# Peripherals.net
KiCad netlist of a schematic drawn in Altium Designer
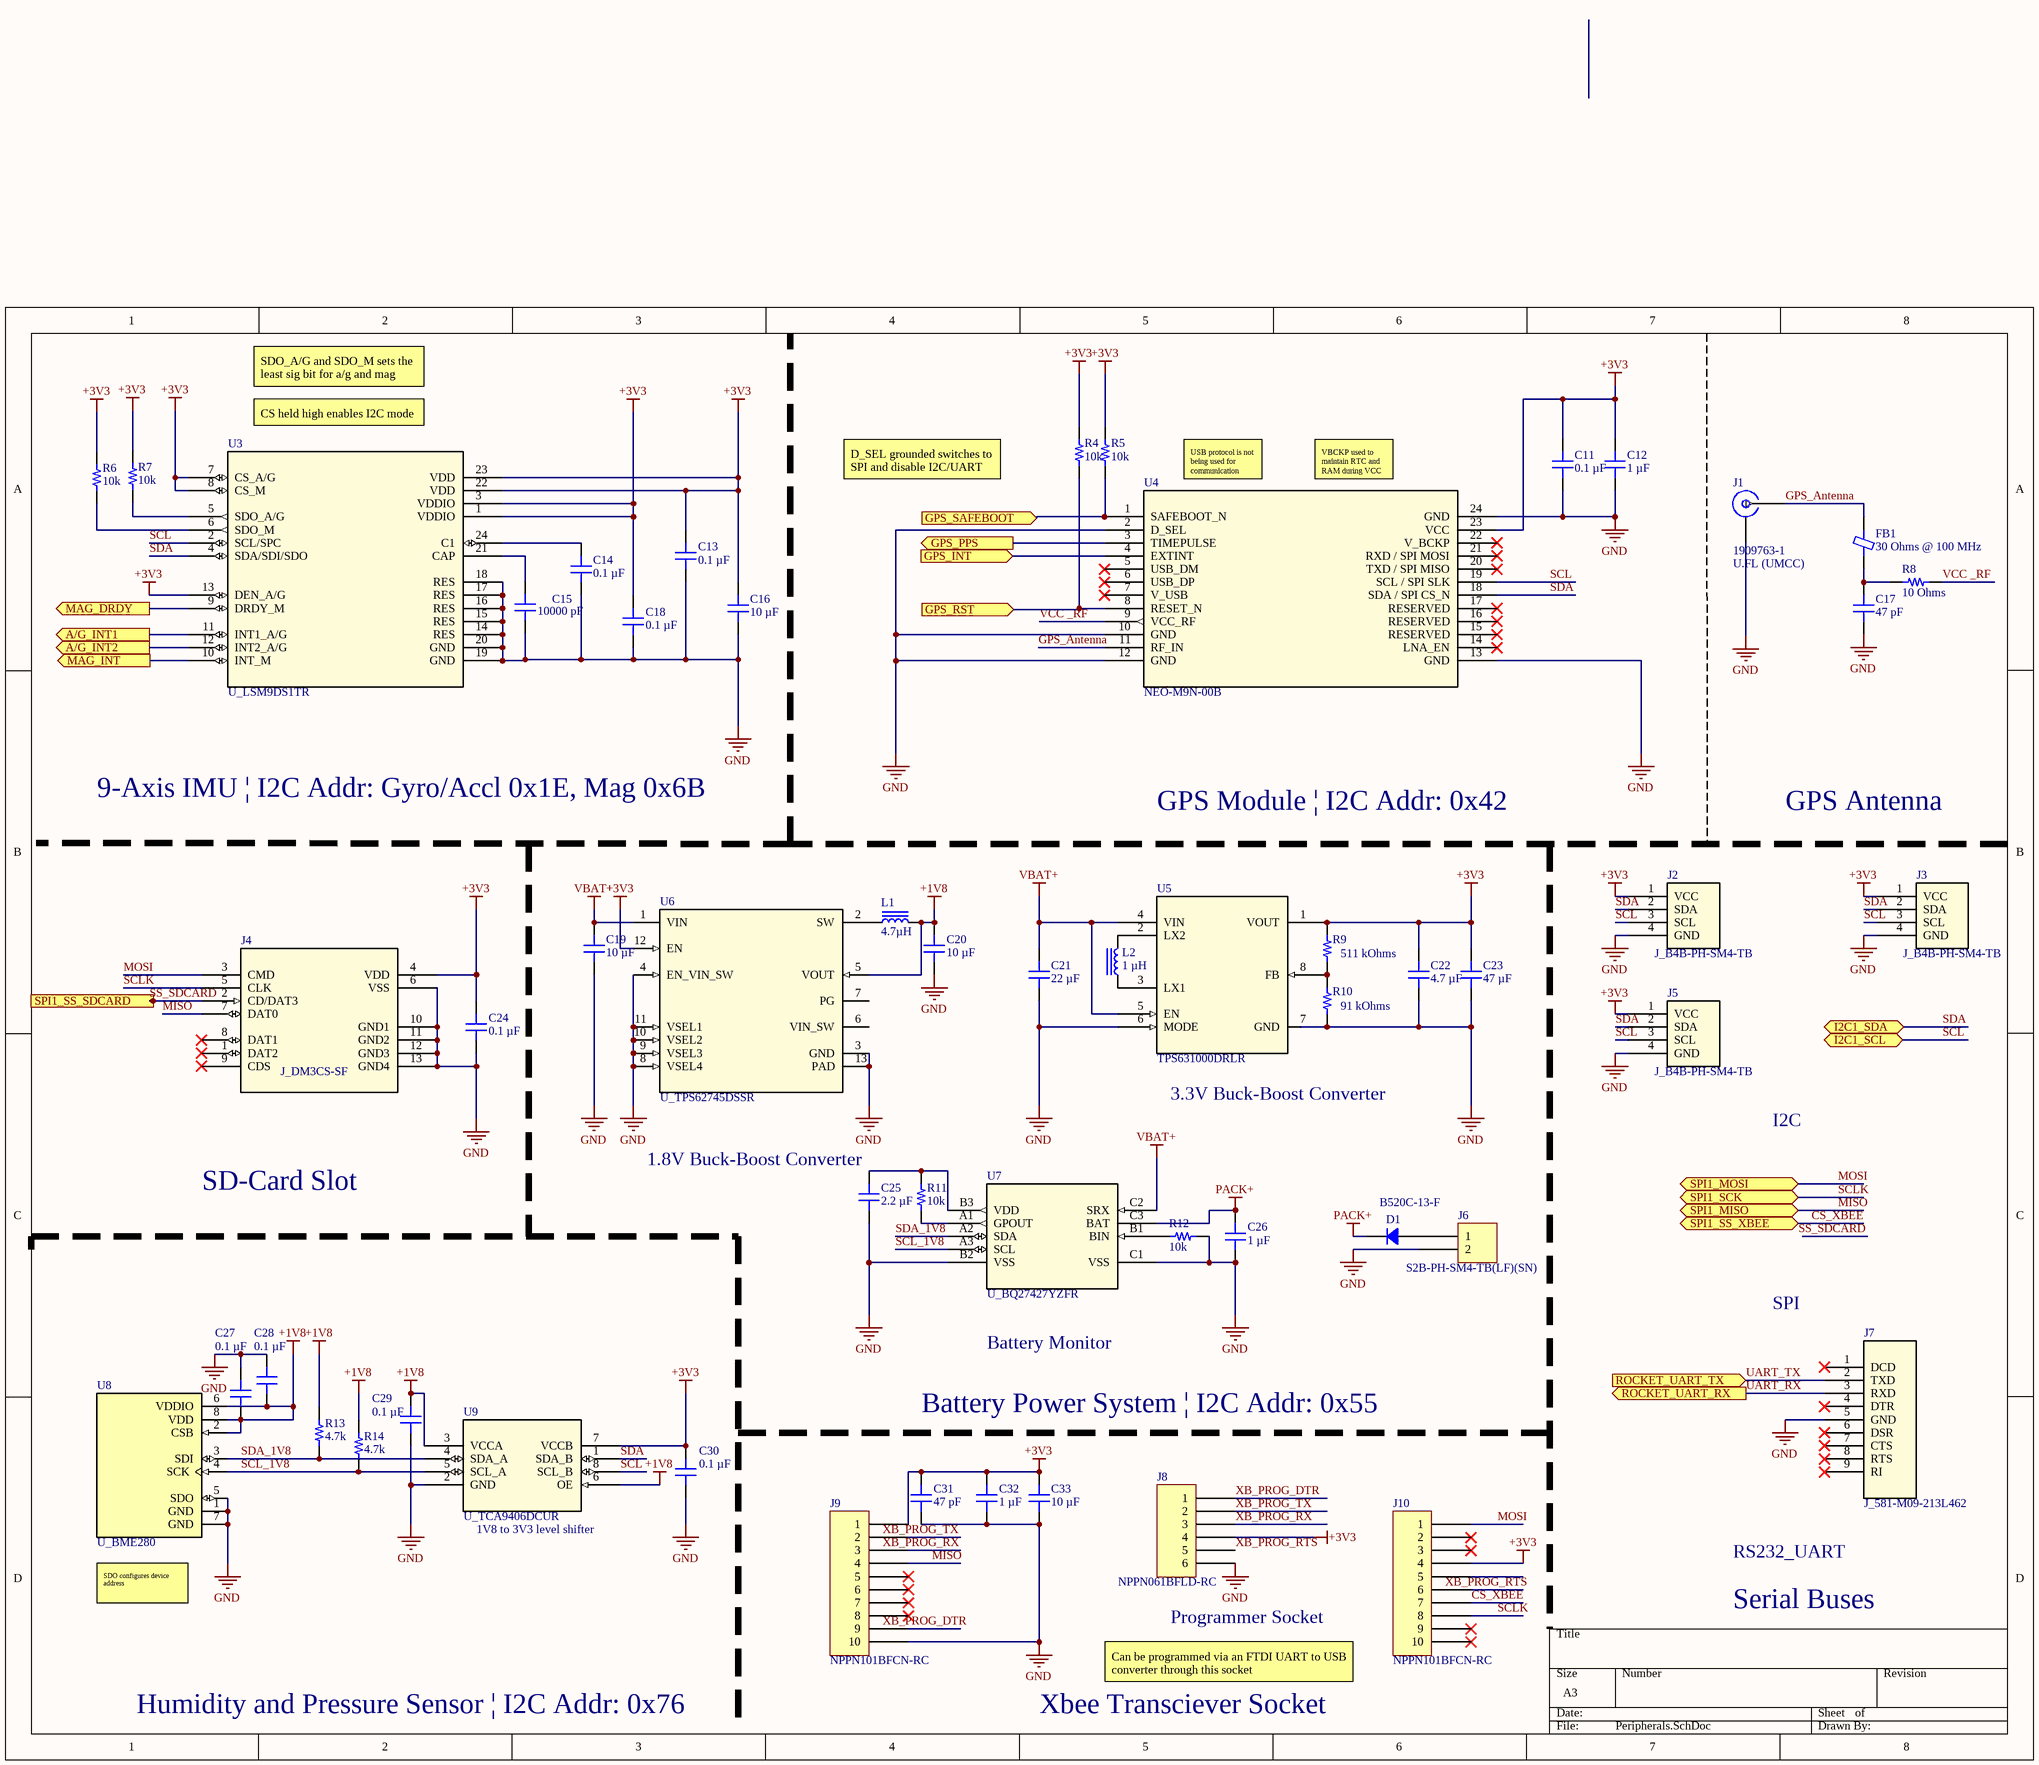
[diagram p0: Peripherals.SchDoc]

(export (version "E")
  (design (tool "Eeschema 10.0.6"))
  (components
    (comp (ref "C11")
      (value "0.1 µF")
      (footprint "CAP 0402_1005")
      (description "CAP CER 100NF 10V X7R 0402")
      (fields
        (field (name "PART NUMBER") "CL05B104KP5VPNC")
        (field (name "MANUFACTURER") "Samsung Electro-Mechanics")
      )
      (libsource (lib "Celestial Altium Library - altium_library") (part "Capacitor"))
    )
    (comp (ref "C12")
      (value "1 µF")
      (footprint "CAP 0402_1005")
      (description "CAP CER 1UF 4V X5R 0402")
      (fields (field (name "PART NUMBER") "KGM05AR50G105KH") (field (name "MANUFACTURER") "KYOCERA AVX"))
      (libsource (lib "Celestial Altium Library - altium_library") (part "Capacitor"))
    )
    (comp (ref "C13")
      (value "0.1 µF")
      (footprint "CAP 0201_0603")
      (description "0201 6.3V X7R 100NF 10%")
      (fields (field (name "PART NUMBER") "02016C104KAT2A") (field (name "MANUFACTURER") "KYOCERA AVX"))
      (libsource (lib "Celestial Altium Library - altium_library") (part "Capacitor"))
    )
    (comp (ref "C14")
      (value "0.1 µF")
      (footprint "CAP 0402_1005")
      (description "CAP CER 100NF 10V X7R 0402")
      (fields
        (field (name "PART NUMBER") "CL05B104KP5VPNC")
        (field (name "MANUFACTURER") "Samsung Electro-Mechanics")
      )
      (libsource (lib "Celestial Altium Library - altium_library") (part "Capacitor"))
    )
    (comp (ref "C15")
      (value "10000 pF")
      (footprint "CAP 0402_1005")
      (description "CAP CER 0402 10NF 16V X7R 10%")
      (fields (field (name "PART NUMBER") "C0402C103K4REC7867") (field (name "MANUFACTURER") "KEMET"))
      (libsource (lib "Celestial Altium Library - altium_library") (part "Capacitor"))
    )
    (comp (ref "C16")
      (value "10 µF")
      (footprint "CAP 0402_1005")
      (description "CAP CER 10UF 4V X5R 0402")
      (fields
        (field (name "PART NUMBER") "GRM155R60G106ME01D")
        (field (name "MANUFACTURER") "Murata Electronics")
      )
      (libsource (lib "Celestial Altium Library - altium_library") (part "Capacitor"))
    )
    (comp (ref "C17")
      (value "47 pF")
      (footprint "CAP 0402_1005")
      (description "CAP CER 47PF 16V NP0 0402")
      (fields (field (name "PART NUMBER") "C0402C470J4GAC7867") (field (name "MANUFACTURER") "KEMET"))
      (libsource (lib "Celestial Altium Library - altium_library") (part "Capacitor"))
    )
    (comp (ref "C18")
      (value "0.1 µF")
      (footprint "CAP 0201_0603")
      (description "0201 6.3V X7R 100NF 10%")
      (fields (field (name "PART NUMBER") "02016C104KAT2A") (field (name "MANUFACTURER") "KYOCERA AVX"))
      (libsource (lib "Celestial Altium Library - altium_library") (part "Capacitor"))
    )
    (comp (ref "C19")
      (value "10 µF")
      (footprint "CAP 0402_1005")
      (description "CAP CER 10UF 4V X5R 0402")
      (fields
        (field (name "PART NUMBER") "GRM155R60G106ME01D")
        (field (name "MANUFACTURER") "Murata Electronics")
      )
      (libsource (lib "Celestial Altium Library - altium_library") (part "Capacitor"))
    )
    (comp (ref "C20")
      (value "10 µF")
      (footprint "CAP 0402_1005")
      (description "CAP CER 10UF 4V X5R 0402")
      (fields
        (field (name "PART NUMBER") "GRM155R60G106ME01D")
        (field (name "MANUFACTURER") "Murata Electronics")
      )
      (libsource (lib "Celestial Altium Library - altium_library") (part "Capacitor"))
    )
    (comp (ref "C21")
      (value "22 µF")
      (footprint "CAP 0402_1005")
      (description "CAP CER 22UF 10V X5R 0402")
      (fields
        (field (name "PART NUMBER") "GRM158R61A226ME15D")
        (field (name "MANUFACTURER") "Murata Electronics")
      )
      (libsource (lib "Celestial Altium Library - altium_library") (part "Capacitor"))
    )
    (comp (ref "C22")
      (value "4.7 µF")
      (footprint "CAP 0603_1608")
      (description "CAP CER 4.7UF 6.3V X6S 0603")
      (fields
        (field (name "PART NUMBER") "GRM185C80J475ME11D")
        (field (name "MANUFACTURER") "Murata Electronics")
      )
      (libsource (lib "Celestial Altium Library - altium_library") (part "Capacitor"))
    )
    (comp (ref "C23")
      (value "47 µF")
      (footprint "CAP 0805_2012")
      (description "CAP CER 47UF 4V X5R 0805")
      (fields (field (name "PART NUMBER") "AMK212BBJ476MD-T") (field (name "MANUFACTURER") "Taiyo Yuden"))
      (libsource (lib "Celestial Altium Library - altium_library") (part "Capacitor"))
    )
    (comp (ref "C24")
      (value "0.1 µF")
      (footprint "CAP 0402_1005")
      (description "CAP CER 100NF 10V X7R 0402")
      (fields
        (field (name "PART NUMBER") "CL05B104KP5VPNC")
        (field (name "MANUFACTURER") "Samsung Electro-Mechanics")
      )
      (libsource (lib "Celestial Altium Library - altium_library") (part "Capacitor"))
    )
    (comp (ref "C25")
      (value "2.2 µF")
      (footprint "CAP 0402_1005")
      (description "CAP CER 2.2UF 35V X5R 0402")
      (fields
        (field (name "PART NUMBER") "GRM155R6YA225KE11D")
        (field (name "MANUFACTURER") "Murata Electronics")
      )
      (libsource (lib "Celestial Altium Library - altium_library") (part "Capacitor"))
    )
    (comp (ref "C26")
      (value "1 µF")
      (footprint "CAP 0402_1005")
      (description "CAP CER 1UF 4V X5R 0402")
      (fields (field (name "PART NUMBER") "KGM05AR50G105KH") (field (name "MANUFACTURER") "KYOCERA AVX"))
      (libsource (lib "Celestial Altium Library - altium_library") (part "Capacitor"))
    )
    (comp (ref "C27")
      (value "0.1 µF")
      (footprint "CAP 0402_1005")
      (description "CAP CER 100NF 10V X7R 0402")
      (fields
        (field (name "PART NUMBER") "CL05B104KP5VPNC")
        (field (name "MANUFACTURER") "Samsung Electro-Mechanics")
      )
      (libsource (lib "Celestial Altium Library - altium_library") (part "Capacitor"))
    )
    (comp (ref "C28")
      (value "0.1 µF")
      (footprint "CAP 0402_1005")
      (description "CAP CER 100NF 10V X7R 0402")
      (fields
        (field (name "PART NUMBER") "CL05B104KP5VPNC")
        (field (name "MANUFACTURER") "Samsung Electro-Mechanics")
      )
      (libsource (lib "Celestial Altium Library - altium_library") (part "Capacitor"))
    )
    (comp (ref "C29")
      (value "0.1 µF")
      (footprint "CAP 0402_1005")
      (description "CAP CER 100NF 10V X7R 0402")
      (fields
        (field (name "PART NUMBER") "CL05B104KP5VPNC")
        (field (name "MANUFACTURER") "Samsung Electro-Mechanics")
      )
      (libsource (lib "Celestial Altium Library - altium_library") (part "Capacitor"))
    )
    (comp (ref "C30")
      (value "0.1 µF")
      (footprint "CAP 0402_1005")
      (description "CAP CER 100NF 10V X7R 0402")
      (fields
        (field (name "PART NUMBER") "CL05B104KP5VPNC")
        (field (name "MANUFACTURER") "Samsung Electro-Mechanics")
      )
      (libsource (lib "Celestial Altium Library - altium_library") (part "Capacitor"))
    )
    (comp (ref "C31")
      (value "47 pF")
      (footprint "CAP 0402_1005")
      (description "CAP CER 47PF 16V NP0 0402")
      (fields (field (name "PART NUMBER") "C0402C470J4GAC7867") (field (name "MANUFACTURER") "KEMET"))
      (libsource (lib "Celestial Altium Library - altium_library") (part "Capacitor"))
    )
    (comp (ref "C32")
      (value "1 µF")
      (footprint "CAP 0402_1005")
      (description "CAP CER 1UF 4V X5R 0402")
      (fields (field (name "PART NUMBER") "KGM05AR50G105KH") (field (name "MANUFACTURER") "KYOCERA AVX"))
      (libsource (lib "Celestial Altium Library - altium_library") (part "Capacitor"))
    )
    (comp (ref "C33")
      (value "10 µF")
      (footprint "CAP 0402_1005")
      (description "CAP CER 10UF 10V X5R 0402")
      (fields
        (field (name "PART NUMBER") "CL05A106MP8NUB8")
        (field (name "MANUFACTURER") "Samsung Electro-Mechanics")
      )
      (libsource (lib "Celestial Altium Library - altium_library") (part "Capacitor"))
    )
    (comp (ref "D1")
      (value "B520C-13-F")
      (footprint "DO214AB SMC")
      (description "DIODE SCHOTTKY 20V 5A SMC")
      (fields (field (name "MANUFACTURER") "Diodes Incorporated"))
      (libsource (lib "Celestial Altium Library - altium_library") (part "Diode"))
    )
    (comp (ref "FB1")
      (value "30 Ohms @ 100 MHz")
      (footprint "FER 0402_1005")
      (description "FERRITE BEAD 30 OHM 0402 1LN")
      (fields
        (field (name "PART NUMBER") "BLM15PE300SH1D")
        (field (name "MANUFACTURER") "Murata Electronics")
      )
      (libsource (lib "Celestial Altium Library - altium_library") (part "Ferrite Chip"))
    )
    (comp (ref "J1")
      (value "1909763-1")
      (footprint "TE C-1909763")
      (description "CONN UMCC JACK STR 50OHM SMD")
      (fields
        (field (name "CONNECTOR STYLE") "U.FL (UMCC)")
        (field (name "MANUFACTURER") "TE Connectivity AMP Connectors")
      )
      (libsource (lib "Celestial Altium Library - altium_library") (part "COAXIAL JACK"))
    )
    (comp (ref "J2")
      (value "J_B4B-PH-SM4-TB")
      (footprint "CONN_B4B-PH-SM4-TB_JST")
      (description "No Description Available")
      (libsource (lib "J_B4B-PH-SM4-TB") (part "J_B4B-PH-SM4-TB"))
    )
    (comp (ref "J3")
      (value "J_B4B-PH-SM4-TB")
      (footprint "CONN_B4B-PH-SM4-TB_JST")
      (description "No Description Available")
      (libsource (lib "J_B4B-PH-SM4-TB") (part "J_B4B-PH-SM4-TB"))
    )
    (comp (ref "J4")
      (value "J_DM3CS-SF")
      (footprint "DM3CS-SF_HIR")
      (description "No Description Available")
      (libsource (lib "J_DM3CS-SF") (part "J_DM3CS-SF"))
    )
    (comp (ref "J5")
      (value "J_B4B-PH-SM4-TB")
      (footprint "CONN_B4B-PH-SM4-TB_JST")
      (description "No Description Available")
      (libsource (lib "J_B4B-PH-SM4-TB") (part "J_B4B-PH-SM4-TB"))
    )
    (comp (ref "J6")
      (value "S2B-PH-SM4-TB(LF)(SN)")
      (footprint "JST S2B-PH-SM4-TB")
      (description "CONN HEADER SMD R/A 2POS 2MM")
      (fields (field (name "MANUFACTURER") "JST Sales America Inc."))
      (libsource (lib "Celestial Altium Library - altium_library") (part "2 Pin"))
    )
    (comp (ref "J7")
      (value "J_581-M09-213L462")
      (footprint "CONN_581-M09-213L462_NRC")
      (description "9 Position D-Type, Micro-D Receptacle, Female Sockets Connector")
      (libsource (lib "J_581-M09-213L462") (part "J_581-M09-213L462"))
    )
    (comp (ref "J8")
      (value "NPPN061BFLD-RC")
      (footprint "SULLINS NPPN061BFLD-RC")
      (description "CONN HDR 6POS 0.079 GOLD SMD")
      (fields (field (name "MANUFACTURER") "Sullins Connector Solutions"))
      (libsource (lib "Celestial Altium Library - altium_library") (part "6 Pin"))
    )
    (comp (ref "J9")
      (value "NPPN101BFCN-RC")
      (footprint "SULLINS NPPN101BFCN")
      (description "CONN HDR 10POS 0.079 GOLD PCB")
      (fields (field (name "MANUFACTURER") "Sullins Connector Solutions"))
      (libsource (lib "Celestial Altium Library - altium_library") (part "10 Pin"))
    )
    (comp (ref "J10")
      (value "NPPN101BFCN-RC")
      (footprint "SULLINS NPPN101BFCN")
      (description "CONN HDR 10POS 0.079 GOLD PCB")
      (fields (field (name "MANUFACTURER") "Sullins Connector Solutions"))
      (libsource (lib "Celestial Altium Library - altium_library") (part "10 Pin"))
    )
    (comp (ref "L1")
      (value "4.7µH")
      (footprint "IND 0603_1608 RF WW")
      (description "FIXED IND 4.7UH 160MA 2.7 OHM")
      (fields (field (name "PART NUMBER") "AISC-0603F-4R7J-T") (field (name "MANUFACTURER") "Abracon LLC"))
      (libsource (lib "Celestial Altium Library - altium_library") (part "Inductor"))
    )
    (comp (ref "L2")
      (value "1 µH")
      (footprint "IND 0806_2016")
      (description "FIXED IND 1UH 1.4A 107 MOHM SMD")
      (fields
        (field (name "PART NUMBER") "LQM2MPN1R0NG0L")
        (field (name "MANUFACTURER") "Murata Electronics")
      )
      (libsource (lib "Celestial Altium Library - altium_library") (part "Inductor"))
    )
    (comp (ref "R4")
      (value "10k")
      (footprint "RES 0402_1005")
      (description "RES 10K OHM 0.1% 1/10W 0402")
      (fields
        (field (name "PART NUMBER") "RP73PF1E10KBTD")
        (field (name "MANUFACTURER") "TE Connectivity Passive Product")
      )
      (libsource (lib "Celestial Altium Library - altium_library") (part "Resistor"))
    )
    (comp (ref "R5")
      (value "10k")
      (footprint "RES 0402_1005")
      (description "RES 10K OHM 0.1% 1/10W 0402")
      (fields
        (field (name "PART NUMBER") "RP73PF1E10KBTD")
        (field (name "MANUFACTURER") "TE Connectivity Passive Product")
      )
      (libsource (lib "Celestial Altium Library - altium_library") (part "Resistor"))
    )
    (comp (ref "R6")
      (value "10k")
      (footprint "RES 0402_1005")
      (description "RES 10K OHM 0.1% 1/10W 0402")
      (fields
        (field (name "PART NUMBER") "RP73PF1E10KBTD")
        (field (name "MANUFACTURER") "TE Connectivity Passive Product")
      )
      (libsource (lib "Celestial Altium Library - altium_library") (part "Resistor"))
    )
    (comp (ref "R7")
      (value "10k")
      (footprint "RES 0402_1005")
      (description "RES 10K OHM 0.1% 1/10W 0402")
      (fields
        (field (name "PART NUMBER") "RP73PF1E10KBTD")
        (field (name "MANUFACTURER") "TE Connectivity Passive Product")
      )
      (libsource (lib "Celestial Altium Library - altium_library") (part "Resistor"))
    )
    (comp (ref "R8")
      (value "10 Ohms")
      (footprint "RES 0402_1005")
      (description "TOTAL LEAD-FREE CHIP RESISTOR SU")
      (fields (field (name "PART NUMBER") "SR0402JR-7W10RP") (field (name "MANUFACTURER") "Yageo"))
      (libsource (lib "Celestial Altium Library - altium_library") (part "Resistor"))
    )
    (comp (ref "R9")
      (value "511 kOhms")
      (footprint "RES 0402_1005")
      (description "RES SMD 511K OHM 1% 1/16W 0402")
      (fields (field (name "PART NUMBER") "CRCW0402511KFKED") (field (name "MANUFACTURER") "Vishay Dale"))
      (libsource (lib "Celestial Altium Library - altium_library") (part "Resistor"))
    )
    (comp (ref "R10")
      (value "91 kOhms")
      (footprint "RES 0402_1005")
      (description "RES SMD 91K OHM 5% 1/16W 0402")
      (fields (field (name "PART NUMBER") "CRCW040291K0JNED") (field (name "MANUFACTURER") "Vishay Dale"))
      (libsource (lib "Celestial Altium Library - altium_library") (part "Resistor"))
    )
    (comp (ref "R11")
      (value "10k")
      (footprint "RES 0402_1005")
      (description "RES 10K OHM 0.1% 1/10W 0402")
      (fields
        (field (name "PART NUMBER") "RP73PF1E10KBTD")
        (field (name "MANUFACTURER") "TE Connectivity Passive Product")
      )
      (libsource (lib "Celestial Altium Library - altium_library") (part "Resistor"))
    )
    (comp (ref "R12")
      (value "10k")
      (footprint "RES 0402_1005")
      (description "RES 10K OHM 0.1% 1/10W 0402")
      (fields
        (field (name "PART NUMBER") "RP73PF1E10KBTD")
        (field (name "MANUFACTURER") "TE Connectivity Passive Product")
      )
      (libsource (lib "Celestial Altium Library - altium_library") (part "Resistor"))
    )
    (comp (ref "R13")
      (value "4.7k")
      (footprint "RES 0201_0603")
      (description "RES SMD 4.7K OHM 1% 1/20W 0201")
      (fields (field (name "PART NUMBER") "CRCW02014K70FKED") (field (name "MANUFACTURER") "Vishay Dale"))
      (libsource (lib "Celestial Altium Library - altium_library") (part "Resistor"))
    )
    (comp (ref "R14")
      (value "4.7k")
      (footprint "RES 0201_0603")
      (description "RES SMD 4.7K OHM 1% 1/20W 0201")
      (fields (field (name "PART NUMBER") "CRCW02014K70FKED") (field (name "MANUFACTURER") "Vishay Dale"))
      (libsource (lib "Celestial Altium Library - altium_library") (part "Resistor"))
    )
    (comp (ref "U3")
      (value "U_LSM9DS1TR")
      (footprint "LGA-24_3X3P5X1_STM")
      (description "No Description Available")
      (libsource (lib "U_LSM9DS1TR") (part "U_LSM9DS1TR"))
    )
    (comp (ref "U4")
      (value "NEO-M9N-00B")
      (footprint "XCVR_NEO-M9N-00B")
      (libsource (lib "U_NEO-M9N-00B") (part "U_NEO-M9N-00B"))
    )
    (comp (ref "U5")
      (value "TPS631000DRLR")
      (footprint "TPS631000DRLR_TEX")
      (description "Non-Isolated PoL Module DC DC Converter 1 Output 1.2 ~ 5.3V 2A 1.6V - 5.5V Input")
      (libsource (lib "U_TPS631000DRLR") (part "TPS631000DRLR"))
    )
    (comp (ref "U6")
      (value "U_TPS62745DSSR")
      (footprint "DSS0012A")
      (description "No Description Available")
      (fields (field (name "PARTNUMBER") "TPS62745DSSR") (field (name "ALTERNATE_PARTNUMBER") "TPS62745DSST"))
      (libsource (lib "U_TPS62745DSSR") (part "U_TPS62745DSSR"))
    )
    (comp (ref "U7")
      (value "U_BQ27427YZFR")
      (footprint "DSBGA9-YZF_TEX")
      (description "No Description Available")
      (libsource (lib "U_BQ27427YZFR") (part "U_BQ27427YZFR"))
    )
    (comp (ref "U8")
      (value "U_BME280")
      (footprint "BME280")
      (description "Humidity, Pressure, Temperature 0 ~ 100% RH I2C, SPI ±3% 1 s Surface Mount")
      (fields (field (name "MP") "BME280"))
      (libsource (lib "U_BME280") (part "U_BME280"))
    )
    (comp (ref "U9")
      (value "U_TCA9406DCUR")
      (footprint "DCU8")
      (description "No Description Available")
      (libsource (lib "U_TCA9406DCUR") (part "U_TCA9406DCUR"))
    )
  )
  (nets
    (net (code "1") (name "+1V8") (class "Default")
      (node (ref "C20") (pin "2") (pinfunction "2_2") (pintype "passive"))
      (node (ref "C27") (pin "2") (pinfunction "2_2") (pintype "passive"))
      (node (ref "C28") (pin "2") (pinfunction "2_2") (pintype "passive"))
      (node (ref "C29") (pin "1") (pinfunction "1_1") (pintype "passive"))
      (node (ref "L1") (pin "2") (pinfunction "2_2") (pintype "passive"))
      (node (ref "R13") (pin "2") (pinfunction "2_2") (pintype "passive"))
      (node (ref "R14") (pin "2") (pinfunction "2_2") (pintype "passive"))
      (node (ref "U6") (pin "5") (pinfunction "VOUT_5") (pintype "input"))
      (node (ref "U8") (pin "2") (pinfunction "CSB_2") (pintype "input"))
      (node (ref "U8") (pin "6") (pinfunction "VDDIO_6") (pintype "power_in"))
      (node (ref "U8") (pin "8") (pinfunction "VDD_8") (pintype "power_in"))
      (node (ref "U9") (pin "3") (pinfunction "VCCA_3") (pintype "power_in"))
      (node (ref "U9") (pin "6") (pinfunction "OE_6") (pintype "input"))
    )
    (net (code "2") (name "+3V3") (class "Default")
      (node (ref "C11") (pin "1") (pinfunction "1_1") (pintype "passive"))
      (node (ref "C12") (pin "2") (pinfunction "2_2") (pintype "passive"))
      (node (ref "C13") (pin "2") (pinfunction "2_2") (pintype "passive"))
      (node (ref "C16") (pin "2") (pinfunction "2_2") (pintype "passive"))
      (node (ref "C18") (pin "2") (pinfunction "2_2") (pintype "passive"))
      (node (ref "C22") (pin "2") (pinfunction "2_2") (pintype "passive"))
      (node (ref "C23") (pin "2") (pinfunction "2_2") (pintype "passive"))
      (node (ref "C24") (pin "2") (pinfunction "2_2") (pintype "passive"))
      (node (ref "C30") (pin "1") (pinfunction "1_1") (pintype "passive"))
      (node (ref "C31") (pin "2") (pinfunction "2_2") (pintype "passive"))
      (node (ref "C32") (pin "2") (pinfunction "2_2") (pintype "passive"))
      (node (ref "C33") (pin "2") (pinfunction "2_2") (pintype "passive"))
      (node (ref "J10") (pin "4") (pinfunction "4_4") (pintype "passive"))
      (node (ref "J2") (pin "1") (pinfunction "VCC_1") (pintype "passive"))
      (node (ref "J3") (pin "1") (pinfunction "VCC_1") (pintype "passive"))
      (node (ref "J4") (pin "4") (pinfunction "VDD_4") (pintype "power_in"))
      (node (ref "J5") (pin "1") (pinfunction "VCC_1") (pintype "passive"))
      (node (ref "J8") (pin "4") (pinfunction "4_4") (pintype "passive"))
      (node (ref "J9") (pin "1") (pinfunction "1_1") (pintype "passive"))
      (node (ref "R4") (pin "1") (pinfunction "1_1") (pintype "passive"))
      (node (ref "R5") (pin "1") (pinfunction "1_1") (pintype "passive"))
      (node (ref "R6") (pin "1") (pinfunction "1_1") (pintype "passive"))
      (node (ref "R7") (pin "1") (pinfunction "1_1") (pintype "passive"))
      (node (ref "R9") (pin "2") (pinfunction "2_2") (pintype "passive"))
      (node (ref "U3") (pin "1") (pinfunction "VDDIO_1") (pintype "power_in"))
      (node (ref "U3") (pin "13") (pinfunction "DEN_A/G_13") (pintype "bidirectional"))
      (node (ref "U3") (pin "22") (pinfunction "VDD_22") (pintype "power_in"))
      (node (ref "U3") (pin "23") (pinfunction "VDD_23") (pintype "power_in"))
      (node (ref "U3") (pin "3") (pinfunction "VDDIO_3") (pintype "power_in"))
      (node (ref "U3") (pin "7") (pinfunction "CS_A/G_7") (pintype "bidirectional"))
      (node (ref "U3") (pin "8") (pinfunction "CS_M_8") (pintype "bidirectional"))
      (node (ref "U4") (pin "23") (pinfunction "VCC_23") (pintype "power_in"))
      (node (ref "U5") (pin "1") (pinfunction "VOUT_1") (pintype "power_in"))
      (node (ref "U6") (pin "12") (pinfunction "EN_12") (pintype "input"))
      (node (ref "U9") (pin "7") (pinfunction "VCCB_7") (pintype "power_in"))
    )
    (net (code "3") (name "/A{slash}G_INT1") (class "Default")
      (node (ref "U3") (pin "11") (pinfunction "INT1_A/G_11") (pintype "bidirectional"))
    )
    (net (code "4") (name "/A{slash}G_INT2") (class "Default")
      (node (ref "U3") (pin "12") (pinfunction "INT2_A/G_12") (pintype "bidirectional"))
    )
    (net (code "5") (name "/CS_XBEE") (class "Default")
      (node (ref "J10") (pin "7") (pinfunction "7_7") (pintype "passive"))
    )
    (net (code "6") (name "/GPS_Antenna") (class "Default")
      (node (ref "FB1") (pin "2") (pinfunction "2_2") (pintype "passive"))
      (node (ref "J1") (pin "S") (pinfunction "SIGNAL_S") (pintype "output"))
      (node (ref "U4") (pin "11") (pinfunction "RF_IN_11") (pintype "passive"))
    )
    (net (code "7") (name "/GPS_INT") (class "Default")
      (node (ref "U4") (pin "4") (pinfunction "EXTINT_4") (pintype "passive"))
    )
    (net (code "8") (name "/GPS_PPS") (class "Default")
      (node (ref "U4") (pin "3") (pinfunction "TIMEPULSE_3") (pintype "passive"))
    )
    (net (code "9") (name "/GPS_RST") (class "Default")
      (node (ref "R4") (pin "2") (pinfunction "2_2") (pintype "passive"))
      (node (ref "U4") (pin "8") (pinfunction "RESET_N_8") (pintype "passive"))
    )
    (net (code "10") (name "/GPS_SAFEBOOT") (class "Default")
      (node (ref "R5") (pin "2") (pinfunction "2_2") (pintype "passive"))
      (node (ref "U4") (pin "1") (pinfunction "SAFEBOOT_N_1") (pintype "passive"))
    )
    (net (code "11") (name "/MAG_DRDY") (class "Default")
      (node (ref "U3") (pin "9") (pinfunction "DRDY_M_9") (pintype "bidirectional"))
    )
    (net (code "12") (name "/MAG_INT") (class "Default")
      (node (ref "U3") (pin "10") (pinfunction "INT_M_10") (pintype "bidirectional"))
    )
    (net (code "13") (name "/MISO") (class "Default")
      (node (ref "J4") (pin "7") (pinfunction "DAT0_7") (pintype "bidirectional"))
      (node (ref "J9") (pin "4") (pinfunction "4_4") (pintype "passive"))
    )
    (net (code "14") (name "/MOSI") (class "Default")
      (node (ref "J10") (pin "1") (pinfunction "1_1") (pintype "passive"))
      (node (ref "J4") (pin "3") (pinfunction "CMD_3") (pintype "passive"))
    )
    (net (code "15") (name "/SCL") (class "Default")
      (node (ref "J2") (pin "3") (pinfunction "SCL_3") (pintype "passive"))
      (node (ref "J3") (pin "3") (pinfunction "SCL_3") (pintype "passive"))
      (node (ref "J5") (pin "3") (pinfunction "SCL_3") (pintype "passive"))
      (node (ref "U3") (pin "2") (pinfunction "SCL/SPC_2") (pintype "bidirectional"))
      (node (ref "U4") (pin "19") (pinfunction "SCL_/_SPI_SLK_19") (pintype "passive"))
      (node (ref "U9") (pin "8") (pinfunction "SCL_B_8") (pintype "bidirectional"))
    )
    (net (code "16") (name "/SCLK") (class "Default")
      (node (ref "J10") (pin "8") (pinfunction "8_8") (pintype "passive"))
      (node (ref "J4") (pin "5") (pinfunction "CLK_5") (pintype "passive"))
    )
    (net (code "17") (name "/SCL_1V8") (class "Default")
      (node (ref "R14") (pin "1") (pinfunction "1_1") (pintype "passive"))
      (node (ref "U7") (pin "A3") (pinfunction "SCL_A3") (pintype "bidirectional"))
      (node (ref "U8") (pin "4") (pinfunction "SCK_4") (pintype "input"))
      (node (ref "U9") (pin "5") (pinfunction "SCL_A_5") (pintype "bidirectional"))
    )
    (net (code "18") (name "/SDA") (class "Default")
      (node (ref "J2") (pin "2") (pinfunction "SDA_2") (pintype "passive"))
      (node (ref "J3") (pin "2") (pinfunction "SDA_2") (pintype "passive"))
      (node (ref "J5") (pin "2") (pinfunction "SDA_2") (pintype "passive"))
      (node (ref "U3") (pin "4") (pinfunction "SDA/SDI/SDO_4") (pintype "bidirectional"))
      (node (ref "U4") (pin "18") (pinfunction "SDA_/_SPI_CS_N_18") (pintype "passive"))
      (node (ref "U9") (pin "1") (pinfunction "SDA_B_1") (pintype "bidirectional"))
    )
    (net (code "19") (name "/SDA_1V8") (class "Default")
      (node (ref "R13") (pin "1") (pinfunction "1_1") (pintype "passive"))
      (node (ref "U7") (pin "A2") (pinfunction "SDA_A2") (pintype "bidirectional"))
      (node (ref "U8") (pin "3") (pinfunction "SDI_3") (pintype "bidirectional"))
      (node (ref "U9") (pin "4") (pinfunction "SDA_A_4") (pintype "bidirectional"))
    )
    (net (code "20") (name "/SS_SDCARD") (class "Default")
      (node (ref "J4") (pin "2") (pinfunction "CD/DAT3_2") (pintype "input"))
    )
    (net (code "21") (name "/UART_RX") (class "Default")
      (node (ref "J7") (pin "3") (pinfunction "RXD_3") (pintype "passive"))
    )
    (net (code "22") (name "/UART_TX") (class "Default")
      (node (ref "J7") (pin "2") (pinfunction "TXD_2") (pintype "passive"))
    )
    (net (code "23") (name "/VCC _RF") (class "Default")
      (node (ref "R8") (pin "2") (pinfunction "2_2") (pintype "passive"))
      (node (ref "U4") (pin "9") (pinfunction "VCC_RF_9") (pintype "output"))
    )
    (net (code "24") (name "/XB_PROG_DTR") (class "Default")
      (node (ref "J8") (pin "1") (pinfunction "1_1") (pintype "passive"))
    )
    (net (code "25") (name "/XB_PROG_RTS") (class "Default")
      (node (ref "J8") (pin "5") (pinfunction "5_5") (pintype "passive"))
    )
    (net (code "26") (name "/XB_PROG_RX") (class "Default")
      (node (ref "J8") (pin "3") (pinfunction "3_3") (pintype "passive"))
    )
    (net (code "27") (name "/XB_PROG_TX") (class "Default")
      (node (ref "J8") (pin "2") (pinfunction "2_2") (pintype "passive"))
    )
    (net (code "28") (name "GND") (class "Default")
      (node (ref "C11") (pin "2") (pinfunction "2_2") (pintype "passive"))
      (node (ref "C12") (pin "1") (pinfunction "1_1") (pintype "passive"))
      (node (ref "C13") (pin "1") (pinfunction "1_1") (pintype "passive"))
      (node (ref "C14") (pin "1") (pinfunction "1_1") (pintype "passive"))
      (node (ref "C15") (pin "1") (pinfunction "1_1") (pintype "passive"))
      (node (ref "C16") (pin "1") (pinfunction "1_1") (pintype "passive"))
      (node (ref "C17") (pin "1") (pinfunction "1_1") (pintype "passive"))
      (node (ref "C18") (pin "1") (pinfunction "1_1") (pintype "passive"))
      (node (ref "C19") (pin "1") (pinfunction "1_1") (pintype "passive"))
      (node (ref "C20") (pin "1") (pinfunction "1_1") (pintype "passive"))
      (node (ref "C21") (pin "1") (pinfunction "1_1") (pintype "passive"))
      (node (ref "C22") (pin "1") (pinfunction "1_1") (pintype "passive"))
      (node (ref "C23") (pin "1") (pinfunction "1_1") (pintype "passive"))
      (node (ref "C24") (pin "1") (pinfunction "1_1") (pintype "passive"))
      (node (ref "C25") (pin "1") (pinfunction "1_1") (pintype "passive"))
      (node (ref "C26") (pin "1") (pinfunction "1_1") (pintype "passive"))
      (node (ref "C27") (pin "1") (pinfunction "1_1") (pintype "passive"))
      (node (ref "C28") (pin "1") (pinfunction "1_1") (pintype "passive"))
      (node (ref "C29") (pin "2") (pinfunction "2_2") (pintype "passive"))
      (node (ref "C30") (pin "2") (pinfunction "2_2") (pintype "passive"))
      (node (ref "C31") (pin "1") (pinfunction "1_1") (pintype "passive"))
      (node (ref "C32") (pin "1") (pinfunction "1_1") (pintype "passive"))
      (node (ref "C33") (pin "1") (pinfunction "1_1") (pintype "passive"))
      (node (ref "J1") (pin "G") (pinfunction "GND_G") (pintype "passive"))
      (node (ref "J2") (pin "4") (pinfunction "GND_4") (pintype "passive"))
      (node (ref "J3") (pin "4") (pinfunction "GND_4") (pintype "passive"))
      (node (ref "J4") (pin "10") (pinfunction "GND1_10") (pintype "power_in"))
      (node (ref "J4") (pin "11") (pinfunction "GND2_11") (pintype "power_in"))
      (node (ref "J4") (pin "12") (pinfunction "GND3_12") (pintype "power_in"))
      (node (ref "J4") (pin "13") (pinfunction "GND4_13") (pintype "power_in"))
      (node (ref "J4") (pin "6") (pinfunction "VSS_6") (pintype "power_in"))
      (node (ref "J5") (pin "4") (pinfunction "GND_4") (pintype "passive"))
      (node (ref "J6") (pin "2") (pinfunction "2_2") (pintype "passive"))
      (node (ref "J7") (pin "5") (pinfunction "GND_5") (pintype "passive"))
      (node (ref "J8") (pin "6") (pinfunction "6_6") (pintype "passive"))
      (node (ref "J9") (pin "10") (pinfunction "10_10") (pintype "passive"))
      (node (ref "R10") (pin "1") (pinfunction "1_1") (pintype "passive"))
      (node (ref "R12") (pin "1") (pinfunction "1_1") (pintype "passive"))
      (node (ref "U3") (pin "14") (pinfunction "RES_14") (pintype "passive"))
      (node (ref "U3") (pin "15") (pinfunction "RES_15") (pintype "passive"))
      (node (ref "U3") (pin "16") (pinfunction "RES_16") (pintype "passive"))
      (node (ref "U3") (pin "17") (pinfunction "RES_17") (pintype "passive"))
      (node (ref "U3") (pin "18") (pinfunction "RES_18") (pintype "passive"))
      (node (ref "U3") (pin "19") (pinfunction "GND_19") (pintype "power_in"))
      (node (ref "U3") (pin "20") (pinfunction "GND_20") (pintype "power_in"))
      (node (ref "U4") (pin "10") (pinfunction "GND_10") (pintype "power_in"))
      (node (ref "U4") (pin "12") (pinfunction "GND_12") (pintype "power_in"))
      (node (ref "U4") (pin "13") (pinfunction "GND_13") (pintype "power_in"))
      (node (ref "U4") (pin "2") (pinfunction "D_SEL_2") (pintype "passive"))
      (node (ref "U4") (pin "24") (pinfunction "GND_24") (pintype "power_in"))
      (node (ref "U5") (pin "6") (pinfunction "MODE_6") (pintype "input"))
      (node (ref "U5") (pin "7") (pinfunction "GND_7") (pintype "power_in"))
      (node (ref "U6") (pin "10") (pinfunction "VSEL2_10") (pintype "input"))
      (node (ref "U6") (pin "11") (pinfunction "VSEL1_11") (pintype "input"))
      (node (ref "U6") (pin "13") (pinfunction "PAD_13") (pintype "passive"))
      (node (ref "U6") (pin "3") (pinfunction "GND_3") (pintype "power_in"))
      (node (ref "U6") (pin "4") (pinfunction "EN_VIN_SW_4") (pintype "input"))
      (node (ref "U6") (pin "8") (pinfunction "VSEL4_8") (pintype "input"))
      (node (ref "U6") (pin "9") (pinfunction "VSEL3_9") (pintype "input"))
      (node (ref "U7") (pin "B2") (pinfunction "VSS_B2") (pintype "power_in"))
      (node (ref "U7") (pin "C1") (pinfunction "VSS_C1") (pintype "power_in"))
      (node (ref "U8") (pin "1") (pinfunction "GND_1") (pintype "power_in"))
      (node (ref "U8") (pin "5") (pinfunction "SDO_5") (pintype "bidirectional"))
      (node (ref "U8") (pin "7") (pinfunction "GND_7") (pintype "power_in"))
      (node (ref "U9") (pin "2") (pinfunction "GND_2") (pintype "power_in"))
    )
    (net (code "29") (name "Net-(C17-Pad2)") (class "Default")
      (node (ref "C17") (pin "2") (pinfunction "2_2") (pintype "passive"))
      (node (ref "FB1") (pin "1") (pinfunction "1_1") (pintype "passive"))
      (node (ref "R8") (pin "1") (pinfunction "1_1") (pintype "passive"))
    )
    (net (code "30") (name "Net-(D1-Pad1)") (class "Default")
      (node (ref "D1") (pin "1") (pinfunction "1_1") (pintype "passive"))
      (node (ref "J6") (pin "1") (pinfunction "1_1") (pintype "passive"))
    )
    (net (code "31") (name "Net-(U3-C1)") (class "Default")
      (node (ref "C14") (pin "2") (pinfunction "2_2") (pintype "passive"))
      (node (ref "U3") (pin "24") (pinfunction "C1_24") (pintype "bidirectional"))
    )
    (net (code "32") (name "Net-(U3-CAP)") (class "Default")
      (node (ref "C15") (pin "2") (pinfunction "2_2") (pintype "passive"))
      (node (ref "U3") (pin "21") (pinfunction "CAP_21") (pintype "passive"))
    )
    (net (code "33") (name "Net-(U3-SDO_A{slash}G)") (class "Default")
      (node (ref "R7") (pin "2") (pinfunction "2_2") (pintype "passive"))
      (node (ref "U3") (pin "5") (pinfunction "SDO_A/G_5") (pintype "output"))
    )
    (net (code "34") (name "Net-(U3-SDO_M)") (class "Default")
      (node (ref "R6") (pin "2") (pinfunction "2_2") (pintype "passive"))
      (node (ref "U3") (pin "6") (pinfunction "SDO_M_6") (pintype "output"))
    )
    (net (code "35") (name "Net-(U5-FB)") (class "Default")
      (node (ref "R10") (pin "2") (pinfunction "2_2") (pintype "passive"))
      (node (ref "R9") (pin "1") (pinfunction "1_1") (pintype "passive"))
      (node (ref "U5") (pin "8") (pinfunction "FB_8") (pintype "input"))
    )
    (net (code "36") (name "Net-(U5-LX1)") (class "Default")
      (node (ref "L2") (pin "1") (pinfunction "1_1") (pintype "passive"))
      (node (ref "U5") (pin "3") (pinfunction "LX1_3") (pintype "power_in"))
    )
    (net (code "37") (name "Net-(U5-LX2)") (class "Default")
      (node (ref "L2") (pin "2") (pinfunction "2_2") (pintype "passive"))
      (node (ref "U5") (pin "2") (pinfunction "LX2_2") (pintype "power_in"))
    )
    (net (code "38") (name "Net-(U6-SW)") (class "Default")
      (node (ref "L1") (pin "1") (pinfunction "1_1") (pintype "passive"))
      (node (ref "U6") (pin "2") (pinfunction "SW_2") (pintype "power_in"))
    )
    (net (code "39") (name "Net-(U7-BIN)") (class "Default")
      (node (ref "R12") (pin "2") (pinfunction "2_2") (pintype "passive"))
      (node (ref "U7") (pin "B1") (pinfunction "BIN_B1") (pintype "input"))
    )
    (net (code "40") (name "Net-(U7-GPOUT)") (class "Default")
      (node (ref "R11") (pin "1") (pinfunction "1_1") (pintype "passive"))
      (node (ref "U7") (pin "A1") (pinfunction "GPOUT_A1") (pintype "output"))
    )
    (net (code "41") (name "Net-(U7-VDD)") (class "Default")
      (node (ref "C25") (pin "2") (pinfunction "2_2") (pintype "passive"))
      (node (ref "R11") (pin "2") (pinfunction "2_2") (pintype "passive"))
      (node (ref "U7") (pin "B3") (pinfunction "VDD_B3") (pintype "output"))
    )
    (net (code "42") (name "PACK+") (class "Default")
      (node (ref "C26") (pin "2") (pinfunction "2_2") (pintype "passive"))
      (node (ref "D1") (pin "2") (pinfunction "2_2") (pintype "passive"))
      (node (ref "U7") (pin "C3") (pinfunction "BAT_C3") (pintype "power_in"))
    )
    (net (code "43") (name "VBAT+") (class "Default")
      (node (ref "C19") (pin "2") (pinfunction "2_2") (pintype "passive"))
      (node (ref "C21") (pin "2") (pinfunction "2_2") (pintype "passive"))
      (node (ref "U5") (pin "4") (pinfunction "VIN_4") (pintype "power_in"))
      (node (ref "U5") (pin "5") (pinfunction "EN_5") (pintype "input"))
      (node (ref "U6") (pin "1") (pinfunction "VIN_1") (pintype "power_in"))
      (node (ref "U7") (pin "C2") (pinfunction "SRX_C2") (pintype "input"))
    )
    (net (code "44") (name "unconnected-(J4-CDS-Pad9)") (class "Default")
      (node (ref "J4") (pin "9") (pinfunction "CDS_9") (pintype "passive+no_connect"))
    )
    (net (code "45") (name "unconnected-(J4-DAT1-Pad8)") (class "Default")
      (node (ref "J4") (pin "8") (pinfunction "DAT1_8") (pintype "bidirectional+no_connect"))
    )
    (net (code "46") (name "unconnected-(J4-DAT2-Pad1)") (class "Default")
      (node (ref "J4") (pin "1") (pinfunction "DAT2_1") (pintype "bidirectional+no_connect"))
    )
    (net (code "47") (name "unconnected-(J7-CTS-Pad7)") (class "Default")
      (node (ref "J7") (pin "7") (pinfunction "CTS_7") (pintype "passive+no_connect"))
    )
    (net (code "48") (name "unconnected-(J7-DCD-Pad1)") (class "Default")
      (node (ref "J7") (pin "1") (pinfunction "DCD_1") (pintype "passive+no_connect"))
    )
    (net (code "49") (name "unconnected-(J7-DSR-Pad6)") (class "Default")
      (node (ref "J7") (pin "6") (pinfunction "DSR_6") (pintype "passive+no_connect"))
    )
    (net (code "50") (name "unconnected-(J7-DTR-Pad4)") (class "Default")
      (node (ref "J7") (pin "4") (pinfunction "DTR_4") (pintype "passive+no_connect"))
    )
    (net (code "51") (name "unconnected-(J7-RI-Pad9)") (class "Default")
      (node (ref "J7") (pin "9") (pinfunction "RI_9") (pintype "passive+no_connect"))
    )
    (net (code "52") (name "unconnected-(J7-RTS-Pad8)") (class "Default")
      (node (ref "J7") (pin "8") (pinfunction "RTS_8") (pintype "passive+no_connect"))
    )
    (net (code "53") (name "unconnected-(J9-Pad2)") (class "Default")
      (node (ref "J9") (pin "2") (pinfunction "2_2") (pintype "passive"))
    )
    (net (code "54") (name "unconnected-(J9-Pad3)") (class "Default")
      (node (ref "J9") (pin "3") (pinfunction "3_3") (pintype "passive"))
    )
    (net (code "55") (name "unconnected-(J9-Pad5)") (class "Default")
      (node (ref "J9") (pin "5") (pinfunction "5_5") (pintype "passive+no_connect"))
    )
    (net (code "56") (name "unconnected-(J9-Pad6)") (class "Default")
      (node (ref "J9") (pin "6") (pinfunction "6_6") (pintype "passive+no_connect"))
    )
    (net (code "57") (name "unconnected-(J9-Pad7)") (class "Default")
      (node (ref "J9") (pin "7") (pinfunction "7_7") (pintype "passive+no_connect"))
    )
    (net (code "58") (name "unconnected-(J9-Pad8)") (class "Default")
      (node (ref "J9") (pin "8") (pinfunction "8_8") (pintype "passive+no_connect"))
    )
    (net (code "59") (name "unconnected-(J9-Pad9)") (class "Default")
      (node (ref "J9") (pin "9") (pinfunction "9_9") (pintype "passive"))
    )
    (net (code "60") (name "unconnected-(J10-Pad2)") (class "Default")
      (node (ref "J10") (pin "2") (pinfunction "2_2") (pintype "passive+no_connect"))
    )
    (net (code "61") (name "unconnected-(J10-Pad3)") (class "Default")
      (node (ref "J10") (pin "3") (pinfunction "3_3") (pintype "passive+no_connect"))
    )
    (net (code "62") (name "unconnected-(J10-Pad5)") (class "Default")
      (node (ref "J10") (pin "5") (pinfunction "5_5") (pintype "passive"))
    )
    (net (code "63") (name "unconnected-(J10-Pad6)") (class "Default")
      (node (ref "J10") (pin "6") (pinfunction "6_6") (pintype "passive"))
    )
    (net (code "64") (name "unconnected-(J10-Pad9)") (class "Default")
      (node (ref "J10") (pin "9") (pinfunction "9_9") (pintype "passive+no_connect"))
    )
    (net (code "65") (name "unconnected-(J10-Pad10)") (class "Default")
      (node (ref "J10") (pin "10") (pinfunction "10_10") (pintype "passive+no_connect"))
    )
    (net (code "66") (name "unconnected-(U4-LNA_EN-Pad14)") (class "Default")
      (node (ref "U4") (pin "14") (pinfunction "LNA_EN_14") (pintype "passive+no_connect"))
    )
    (net (code "67") (name "unconnected-(U4-RESERVED-Pad15)") (class "Default")
      (node (ref "U4") (pin "15") (pinfunction "RESERVED_15") (pintype "passive+no_connect"))
    )
    (net (code "68") (name "unconnected-(U4-RESERVED-Pad16)") (class "Default")
      (node (ref "U4") (pin "16") (pinfunction "RESERVED_16") (pintype "passive+no_connect"))
    )
    (net (code "69") (name "unconnected-(U4-RESERVED-Pad17)") (class "Default")
      (node (ref "U4") (pin "17") (pinfunction "RESERVED_17") (pintype "passive+no_connect"))
    )
    (net (code "70") (name "unconnected-(U4-RXD_{slash}_SPI_MOSI-Pad21)") (class "Default")
      (node (ref "U4") (pin "21") (pinfunction "RXD_/_SPI_MOSI_21") (pintype "passive+no_connect"))
    )
    (net (code "71") (name "unconnected-(U4-TXD_{slash}_SPI_MISO-Pad20)") (class "Default")
      (node (ref "U4") (pin "20") (pinfunction "TXD_/_SPI_MISO_20") (pintype "passive+no_connect"))
    )
    (net (code "72") (name "unconnected-(U4-USB_DM-Pad5)") (class "Default")
      (node (ref "U4") (pin "5") (pinfunction "USB_DM_5") (pintype "passive+no_connect"))
    )
    (net (code "73") (name "unconnected-(U4-USB_DP-Pad6)") (class "Default")
      (node (ref "U4") (pin "6") (pinfunction "USB_DP_6") (pintype "passive+no_connect"))
    )
    (net (code "74") (name "unconnected-(U4-V_BCKP-Pad22)") (class "Default")
      (node (ref "U4") (pin "22") (pinfunction "V_BCKP_22") (pintype "passive+no_connect"))
    )
    (net (code "75") (name "unconnected-(U4-V_USB-Pad7)") (class "Default")
      (node (ref "U4") (pin "7") (pinfunction "V_USB_7") (pintype "passive+no_connect"))
    )
    (net (code "76") (name "unconnected-(U6-PG-Pad7)") (class "Default")
      (node (ref "U6") (pin "7") (pinfunction "PG_7") (pintype "open_collector"))
    )
    (net (code "77") (name "unconnected-(U6-VIN_SW-Pad6)") (class "Default")
      (node (ref "U6") (pin "6") (pinfunction "VIN_SW_6") (pintype "power_in"))
    )
  )
)
